# boxer_RS485.net
KiCad netlist of a schematic drawn in Altium Designer
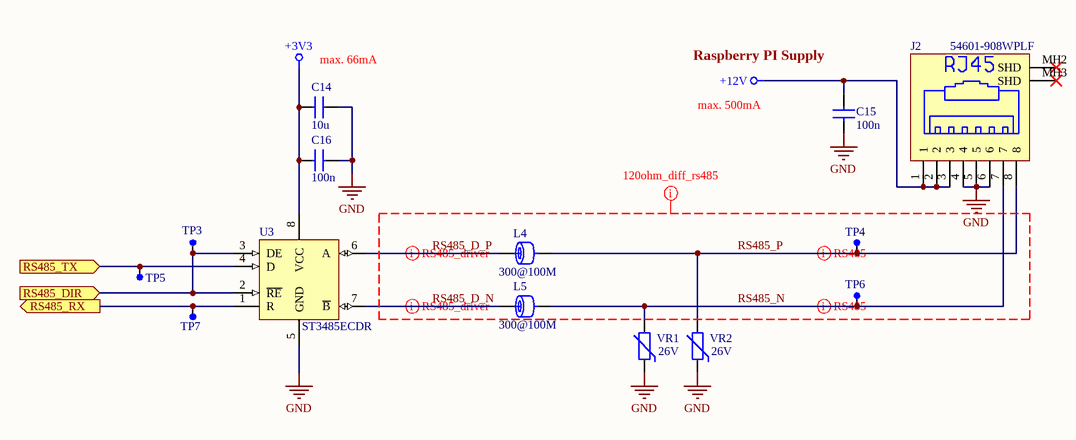
[diagram p0: boxer_RS485.SchDoc]

(export (version "E")
  (design (tool "Eeschema 10.0.6"))
  (components
    (comp (ref "C14")
      (value "10u")
      (footprint "C_1206")
      (description "Capacitor")
      (fields (field (name "Comment") "TME: CL31A226MOCLNNC"))
      (libsource (lib "boxer_pas") (part "Capacitor"))
    )
    (comp (ref "C15")
      (value "100n")
      (footprint "C_0805")
      (description "Capacitor")
      (libsource (lib "boxer_pas") (part "Capacitor"))
    )
    (comp (ref "C16")
      (value "100n")
      (footprint "C_0805")
      (description "Capacitor")
      (libsource (lib "boxer_pas") (part "Capacitor"))
    )
    (comp (ref "J2")
      (value "54601-908WPLF")
      (footprint "RJ45_54601-908WPLF")
      (description "RJ45 Socket, 8pin, No Key, Molex MX-95001-2881")
      (libsource (lib "boxer_mechanical") (part "RJ45-8"))
    )
    (comp (ref "L4")
      (value "300@100M")
      (footprint "L_0805")
      (description "Ferrite Bead")
      (fields (field (name "Comment") "742792031"))
      (libsource (lib "boxer_pas") (part "FB"))
    )
    (comp (ref "L5")
      (value "300@100M")
      (footprint "L_0805")
      (description "Ferrite Bead")
      (fields (field (name "Comment") "742792031"))
      (libsource (lib "boxer_pas") (part "FB"))
    )
    (comp (ref "TP3")
      (value "TEST PAD")
      (footprint "PIN")
      (description "PAD 1.5mm")
      (libsource (lib "boxer_mechanical") (part "TEST_PAD"))
    )
    (comp (ref "TP4")
      (value "TEST PAD")
      (footprint "PIN")
      (description "PAD 1.5mm")
      (libsource (lib "boxer_mechanical") (part "TEST_PAD"))
    )
    (comp (ref "TP5")
      (value "TEST PAD")
      (footprint "PIN")
      (description "PAD 1.5mm")
      (libsource (lib "boxer_mechanical") (part "TEST_PAD"))
    )
    (comp (ref "TP6")
      (value "TEST PAD")
      (footprint "PIN")
      (description "PAD 1.5mm")
      (libsource (lib "boxer_mechanical") (part "TEST_PAD"))
    )
    (comp (ref "TP7")
      (value "TEST PAD")
      (footprint "PIN")
      (description "PAD 1.5mm")
      (libsource (lib "boxer_mechanical") (part "TEST_PAD"))
    )
    (comp (ref "U3")
      (value "ST3485ECDR")
      (footprint "SO8")
      (description "RS-422/RS-485 Interface IC Hi-Spd Lo Pwr Trans")
      (libsource (lib "boxer_ic") (part "ST485BDR"))
    )
    (comp (ref "VR1")
      (value "26V")
      (footprint "VR_0805")
      (description "34.5V 20A Varistor 1 Circuit Surface Mount, MLCV 0805 (2012 Metric)")
      (fields (field (name "Comment") "AMCV-0805-260-C800N-T"))
      (libsource (lib "boxer_pas") (part "Varistor"))
    )
    (comp (ref "VR2")
      (value "26V")
      (footprint "VR_0805")
      (description "34.5V 20A Varistor 1 Circuit Surface Mount, MLCV 0805 (2012 Metric)")
      (fields (field (name "Comment") "AMCV-0805-260-C800N-T"))
      (libsource (lib "boxer_pas") (part "Varistor"))
    )
  )
  (nets
    (net (code "1") (name "+3V3") (class "Default")
      (node (ref "C14") (pin "2") (pinfunction "2_2") (pintype "passive"))
      (node (ref "C16") (pin "1") (pinfunction "1_1") (pintype "passive"))
      (node (ref "U3") (pin "8") (pinfunction "VCC_8") (pintype "power_in"))
    )
    (net (code "2") (name "+12V") (class "Default")
      (node (ref "C15") (pin "1") (pinfunction "1_1") (pintype "passive"))
      (node (ref "J2") (pin "1") (pinfunction "1_1") (pintype "passive"))
      (node (ref "J2") (pin "2") (pinfunction "2_2") (pintype "passive"))
      (node (ref "J2") (pin "3") (pinfunction "3_3") (pintype "passive"))
    )
    (net (code "3") (name "/RS485_DIR") (class "Default")
      (node (ref "TP3") (pin "1") (pinfunction "1_1") (pintype "passive"))
      (node (ref "U3") (pin "2") (pinfunction "~{RE}_2") (pintype "input"))
      (node (ref "U3") (pin "3") (pinfunction "DE_3") (pintype "input"))
    )
    (net (code "4") (name "/RS485_D_N") (class "Default")
      (node (ref "L5") (pin "1") (pinfunction "1_1") (pintype "passive"))
      (node (ref "U3") (pin "7") (pinfunction "~{B}_7") (pintype "bidirectional"))
    )
    (net (code "5") (name "/RS485_D_P") (class "Default")
      (node (ref "L4") (pin "1") (pinfunction "1_1") (pintype "passive"))
      (node (ref "U3") (pin "6") (pinfunction "A_6") (pintype "bidirectional"))
    )
    (net (code "6") (name "/RS485_N") (class "Default")
      (node (ref "J2") (pin "7") (pinfunction "7_7") (pintype "passive"))
      (node (ref "L5") (pin "2") (pinfunction "2_2") (pintype "passive"))
      (node (ref "TP6") (pin "1") (pinfunction "1_1") (pintype "passive"))
      (node (ref "VR1") (pin "1") (pinfunction "1_1") (pintype "passive"))
    )
    (net (code "7") (name "/RS485_P") (class "Default")
      (node (ref "J2") (pin "8") (pinfunction "8_8") (pintype "passive"))
      (node (ref "L4") (pin "2") (pinfunction "2_2") (pintype "passive"))
      (node (ref "TP4") (pin "1") (pinfunction "1_1") (pintype "passive"))
      (node (ref "VR2") (pin "1") (pinfunction "1_1") (pintype "passive"))
    )
    (net (code "8") (name "/RS485_RX") (class "Default")
      (node (ref "TP7") (pin "1") (pinfunction "1_1") (pintype "passive"))
      (node (ref "U3") (pin "1") (pinfunction "R_1") (pintype "tri_state"))
    )
    (net (code "9") (name "/RS485_TX") (class "Default")
      (node (ref "TP5") (pin "1") (pinfunction "1_1") (pintype "passive"))
      (node (ref "U3") (pin "4") (pinfunction "D_4") (pintype "input"))
    )
    (net (code "10") (name "GND") (class "Default")
      (node (ref "C14") (pin "1") (pinfunction "1_1") (pintype "passive"))
      (node (ref "C15") (pin "2") (pinfunction "2_2") (pintype "passive"))
      (node (ref "C16") (pin "2") (pinfunction "2_2") (pintype "passive"))
      (node (ref "J2") (pin "4") (pinfunction "4_4") (pintype "passive"))
      (node (ref "J2") (pin "5") (pinfunction "5_5") (pintype "passive"))
      (node (ref "J2") (pin "6") (pinfunction "6_6") (pintype "passive"))
      (node (ref "U3") (pin "5") (pinfunction "GND_5") (pintype "power_in"))
      (node (ref "VR1") (pin "2") (pinfunction "2_2") (pintype "passive"))
      (node (ref "VR2") (pin "2") (pinfunction "2_2") (pintype "passive"))
    )
    (net (code "11") (name "unconnected-(J2-SHD-PadMH2)") (class "Default")
      (node (ref "J2") (pin "MH2") (pinfunction "SHD_MH2") (pintype "passive+no_connect"))
    )
    (net (code "12") (name "unconnected-(J2-SHD-PadMH3)") (class "Default")
      (node (ref "J2") (pin "MH3") (pinfunction "SHD_MH3") (pintype "passive+no_connect"))
    )
  )
)
